# sim900.net
KiCad netlist of a schematic drawn in EAGLE
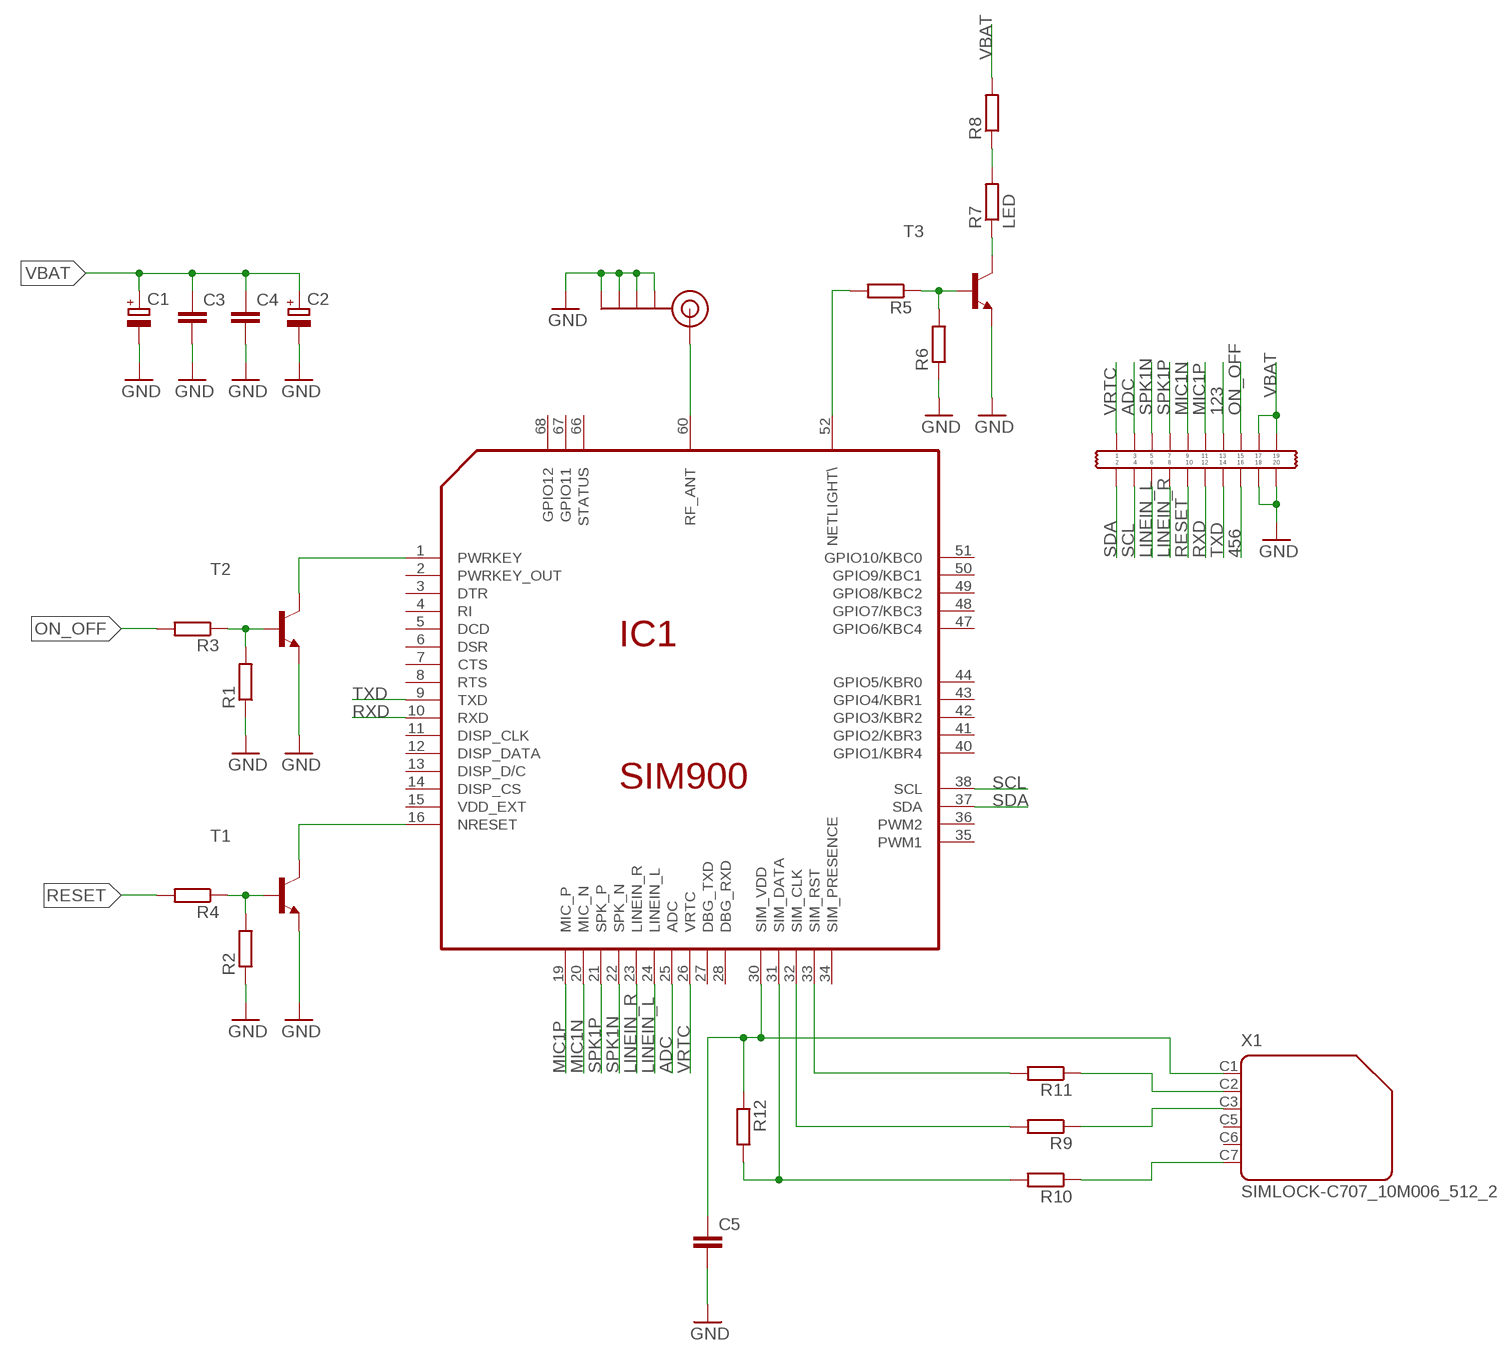
[diagram p0: schematic, sheet 1]

(export (version "E")
  (design (tool "Eeschema 10.0.6"))
  (components
    (comp (ref "C1")
      (value "CPOL-EUSMCD")
      (footprint "eagle-import:SMC_D")
      (libsource (lib "eagle-import") (part "CPOL-EUSMCD"))
    )
    (comp (ref "C2")
      (value "CPOL-EUSMCD")
      (footprint "eagle-import:SMC_D")
      (libsource (lib "eagle-import") (part "CPOL-EUSMCD"))
    )
    (comp (ref "C3")
      (value "C-EUC0805K")
      (footprint "eagle-import:C0805K")
      (libsource (lib "eagle-import") (part "C-EUC0805K"))
    )
    (comp (ref "C4")
      (value "C-EUC0805K")
      (footprint "eagle-import:C0805K")
      (libsource (lib "eagle-import") (part "C-EUC0805K"))
    )
    (comp (ref "C5")
      (value "C-EUC1206K")
      (footprint "eagle-import:C1206K")
      (libsource (lib "eagle-import") (part "C-EUC1206K"))
    )
    (comp (ref "IC1")
      (value "SIM900")
      (footprint "eagle-import:SIM900")
      (libsource (lib "eagle-import") (part "SIM900"))
    )
    (comp (ref "J$1")
      (value "SMA_EDGE")
      (footprint "eagle-import:SMA-EDGE")
      (libsource (lib "eagle-import") (part "SMA_EDGE"))
    )
    (comp (ref "R1")
      (value "R-EU_R0805")
      (footprint "eagle-import:R0805")
      (libsource (lib "eagle-import") (part "R-EU_R0805"))
    )
    (comp (ref "R2")
      (value "R-EU_R0805")
      (footprint "eagle-import:R0805")
      (libsource (lib "eagle-import") (part "R-EU_R0805"))
    )
    (comp (ref "R3")
      (value "R-EU_R0805")
      (footprint "eagle-import:R0805")
      (libsource (lib "eagle-import") (part "R-EU_R0805"))
    )
    (comp (ref "R4")
      (value "R-EU_R0805")
      (footprint "eagle-import:R0805")
      (libsource (lib "eagle-import") (part "R-EU_R0805"))
    )
    (comp (ref "R5")
      (value "R-EU_R0805")
      (footprint "eagle-import:R0805")
      (libsource (lib "eagle-import") (part "R-EU_R0805"))
    )
    (comp (ref "R6")
      (value "R-EU_R0805")
      (footprint "eagle-import:R0805")
      (libsource (lib "eagle-import") (part "R-EU_R0805"))
    )
    (comp (ref "R7")
      (value "LED")
      (footprint "eagle-import:R0805")
      (libsource (lib "eagle-import") (part "R-EU_R0805"))
    )
    (comp (ref "R8")
      (value "R-EU_R0805")
      (footprint "eagle-import:R0805")
      (libsource (lib "eagle-import") (part "R-EU_R0805"))
    )
    (comp (ref "R9")
      (value "R-EU_R0805")
      (footprint "eagle-import:R0805")
      (libsource (lib "eagle-import") (part "R-EU_R0805"))
    )
    (comp (ref "R10")
      (value "R-EU_R0805")
      (footprint "eagle-import:R0805")
      (libsource (lib "eagle-import") (part "R-EU_R0805"))
    )
    (comp (ref "R11")
      (value "R-EU_R0805")
      (footprint "eagle-import:R0805")
      (libsource (lib "eagle-import") (part "R-EU_R0805"))
    )
    (comp (ref "R12")
      (value "R-EU_R0805")
      (footprint "eagle-import:R0805")
      (libsource (lib "eagle-import") (part "R-EU_R0805"))
    )
    (comp (ref "T1")
      (value "-NPN-SOT23-EBC")
      (footprint "eagle-import:SOT23-EBC")
      (libsource (lib "eagle-import") (part "-NPN-SOT23-EBC"))
    )
    (comp (ref "T2")
      (value "-NPN-SOT23-EBC")
      (footprint "eagle-import:SOT23-EBC")
      (libsource (lib "eagle-import") (part "-NPN-SOT23-EBC"))
    )
    (comp (ref "T3")
      (value "-NPN-SOT23-EBC")
      (footprint "eagle-import:SOT23-EBC")
      (libsource (lib "eagle-import") (part "-NPN-SOT23-EBC"))
    )
    (comp (ref "U$1")
      (value "2X10")
      (footprint "eagle-import:2X10")
      (libsource (lib "eagle-import") (part "2X10"))
    )
    (comp (ref "X1")
      (value "SIMLOCK-C707_10M006_512_2")
      (footprint "eagle-import:C707_10M006_512_2")
      (libsource (lib "eagle-import") (part "SIMLOCK-C707_10M006_512_2"))
    )
  )
  (nets
    (net (code "1") (name "/123") (class "Default")
      (node (ref "U$1") (pin "T13") (pinfunction "C13_T13") (pintype "bidirectional"))
    )
    (net (code "2") (name "/456") (class "Default")
      (node (ref "U$1") (pin "B16") (pinfunction "C16_B16") (pintype "bidirectional"))
    )
    (net (code "3") (name "/ADC") (class "Default")
      (node (ref "IC1") (pin "25") (pinfunction "ADC_25") (pintype "bidirectional"))
      (node (ref "U$1") (pin "T3") (pinfunction "C3_T3") (pintype "bidirectional"))
    )
    (net (code "4") (name "/LINEIN_L") (class "Default")
      (node (ref "IC1") (pin "24") (pinfunction "LINEIN_L_24") (pintype "bidirectional"))
      (node (ref "U$1") (pin "B6") (pinfunction "C6_B6") (pintype "bidirectional"))
    )
    (net (code "5") (name "/LINEIN_R") (class "Default")
      (node (ref "IC1") (pin "23") (pinfunction "LINEIN_R_23") (pintype "bidirectional"))
      (node (ref "U$1") (pin "B8") (pinfunction "C8_B8") (pintype "bidirectional"))
    )
    (net (code "6") (name "/MIC1N") (class "Default")
      (node (ref "IC1") (pin "20") (pinfunction "MIC_N_20") (pintype "bidirectional"))
      (node (ref "U$1") (pin "T9") (pinfunction "C9_T9") (pintype "bidirectional"))
    )
    (net (code "7") (name "/MIC1P") (class "Default")
      (node (ref "IC1") (pin "19") (pinfunction "MIC_P_19") (pintype "bidirectional"))
      (node (ref "U$1") (pin "T11") (pinfunction "C11_T11") (pintype "bidirectional"))
    )
    (net (code "8") (name "/RXD") (class "Default")
      (node (ref "IC1") (pin "10") (pinfunction "RXD_10") (pintype "bidirectional"))
      (node (ref "U$1") (pin "B12") (pinfunction "C12_B12") (pintype "bidirectional"))
    )
    (net (code "9") (name "/SCL") (class "Default")
      (node (ref "IC1") (pin "38") (pinfunction "SCL_38") (pintype "bidirectional"))
      (node (ref "U$1") (pin "B4") (pinfunction "C4_B4") (pintype "bidirectional"))
    )
    (net (code "10") (name "/SDA") (class "Default")
      (node (ref "IC1") (pin "37") (pinfunction "SDA_37") (pintype "bidirectional"))
      (node (ref "U$1") (pin "B2") (pinfunction "C2_B2") (pintype "bidirectional"))
    )
    (net (code "11") (name "/SPK1N") (class "Default")
      (node (ref "IC1") (pin "22") (pinfunction "SPK_N_22") (pintype "bidirectional"))
      (node (ref "U$1") (pin "T5") (pinfunction "C5_T5") (pintype "bidirectional"))
    )
    (net (code "12") (name "/SPK1P") (class "Default")
      (node (ref "IC1") (pin "21") (pinfunction "SPK_P_21") (pintype "bidirectional"))
      (node (ref "U$1") (pin "T7") (pinfunction "C7_T7") (pintype "bidirectional"))
    )
    (net (code "13") (name "/TXD") (class "Default")
      (node (ref "IC1") (pin "9") (pinfunction "TXD_9") (pintype "bidirectional"))
      (node (ref "U$1") (pin "B14") (pinfunction "C14_B14") (pintype "bidirectional"))
    )
    (net (code "14") (name "/VRTC") (class "Default")
      (node (ref "IC1") (pin "26") (pinfunction "VRTC_26") (pintype "bidirectional"))
      (node (ref "U$1") (pin "T1") (pinfunction "C1_T1") (pintype "bidirectional"))
    )
    (net (code "15") (name "GND") (class "Default")
      (node (ref "C1") (pin "-") (pinfunction "-_-") (pintype "passive"))
      (node (ref "C2") (pin "-") (pinfunction "-_-") (pintype "passive"))
      (node (ref "C3") (pin "2") (pinfunction "2_2") (pintype "passive"))
      (node (ref "C4") (pin "2") (pinfunction "2_2") (pintype "passive"))
      (node (ref "C5") (pin "2") (pinfunction "2_2") (pintype "passive"))
      (node (ref "J$1") (pin "GND@0") (pinfunction "GND_GND@0") (pintype "bidirectional"))
      (node (ref "J$1") (pin "GND@1") (pinfunction "GND_GND@1") (pintype "bidirectional"))
      (node (ref "J$1") (pin "GND@2") (pinfunction "GND_GND@2") (pintype "bidirectional"))
      (node (ref "J$1") (pin "GND@3") (pinfunction "GND_GND@3") (pintype "bidirectional"))
      (node (ref "R1") (pin "1") (pinfunction "1_1") (pintype "passive"))
      (node (ref "R2") (pin "1") (pinfunction "1_1") (pintype "passive"))
      (node (ref "R6") (pin "1") (pinfunction "1_1") (pintype "passive"))
      (node (ref "T1") (pin "E") (pinfunction "E_E") (pintype "passive"))
      (node (ref "T2") (pin "E") (pinfunction "E_E") (pintype "passive"))
      (node (ref "T3") (pin "E") (pinfunction "E_E") (pintype "passive"))
      (node (ref "U$1") (pin "B18") (pinfunction "C18_B18") (pintype "bidirectional"))
      (node (ref "U$1") (pin "B20") (pinfunction "C20_B20") (pintype "bidirectional"))
    )
    (net (code "16") (name "Net-(IC1A-NETLIGHT\\)") (class "Default")
      (node (ref "IC1") (pin "52") (pinfunction "NETLIGHT\\_52") (pintype "bidirectional"))
      (node (ref "R5") (pin "2") (pinfunction "2_2") (pintype "passive"))
    )
    (net (code "17") (name "Net-(IC1A-NRESET)") (class "Default")
      (node (ref "IC1") (pin "16") (pinfunction "NRESET_16") (pintype "bidirectional"))
      (node (ref "T1") (pin "C") (pinfunction "C_C") (pintype "passive"))
    )
    (net (code "18") (name "Net-(IC1A-PWRKEY)") (class "Default")
      (node (ref "IC1") (pin "1") (pinfunction "PWRKEY_1") (pintype "bidirectional"))
      (node (ref "T2") (pin "C") (pinfunction "C_C") (pintype "passive"))
    )
    (net (code "19") (name "Net-(IC1A-RF_ANT)") (class "Default")
      (node (ref "IC1") (pin "60") (pinfunction "RF_ANT_60") (pintype "bidirectional"))
      (node (ref "J$1") (pin "SIG") (pinfunction "SIGNAL_SIG") (pintype "bidirectional"))
    )
    (net (code "20") (name "Net-(IC1A-SIM_CLK)") (class "Default")
      (node (ref "IC1") (pin "32") (pinfunction "SIM_CLK_32") (pintype "bidirectional"))
      (node (ref "R9") (pin "2") (pinfunction "2_2") (pintype "passive"))
    )
    (net (code "21") (name "Net-(IC1A-SIM_DATA)") (class "Default")
      (node (ref "IC1") (pin "31") (pinfunction "SIM_DATA_31") (pintype "bidirectional"))
      (node (ref "R10") (pin "2") (pinfunction "2_2") (pintype "passive"))
      (node (ref "R12") (pin "2") (pinfunction "2_2") (pintype "passive"))
    )
    (net (code "22") (name "Net-(IC1A-SIM_RST)") (class "Default")
      (node (ref "IC1") (pin "33") (pinfunction "SIM_RST_33") (pintype "bidirectional"))
      (node (ref "R11") (pin "2") (pinfunction "2_2") (pintype "passive"))
    )
    (net (code "23") (name "Net-(IC1A-SIM_VDD)") (class "Default")
      (node (ref "C5") (pin "1") (pinfunction "1_1") (pintype "passive"))
      (node (ref "IC1") (pin "30") (pinfunction "SIM_VDD_30") (pintype "bidirectional"))
      (node (ref "R12") (pin "1") (pinfunction "1_1") (pintype "passive"))
      (node (ref "X1") (pin "C1") (pinfunction "1_C1") (pintype "passive"))
    )
    (net (code "24") (name "Net-(R1-Pad2)") (class "Default")
      (node (ref "R1") (pin "2") (pinfunction "2_2") (pintype "passive"))
      (node (ref "R3") (pin "1") (pinfunction "1_1") (pintype "passive"))
      (node (ref "T2") (pin "B") (pinfunction "B_B") (pintype "passive"))
    )
    (net (code "25") (name "Net-(R2-Pad2)") (class "Default")
      (node (ref "R2") (pin "2") (pinfunction "2_2") (pintype "passive"))
      (node (ref "R4") (pin "1") (pinfunction "1_1") (pintype "passive"))
      (node (ref "T1") (pin "B") (pinfunction "B_B") (pintype "passive"))
    )
    (net (code "26") (name "Net-(R5-Pad1)") (class "Default")
      (node (ref "R5") (pin "1") (pinfunction "1_1") (pintype "passive"))
      (node (ref "R6") (pin "2") (pinfunction "2_2") (pintype "passive"))
      (node (ref "T3") (pin "B") (pinfunction "B_B") (pintype "passive"))
    )
    (net (code "27") (name "Net-(R7-Pad1)") (class "Default")
      (node (ref "R7") (pin "1") (pinfunction "1_1") (pintype "passive"))
      (node (ref "T3") (pin "C") (pinfunction "C_C") (pintype "passive"))
    )
    (net (code "28") (name "Net-(R7-Pad2)") (class "Default")
      (node (ref "R7") (pin "2") (pinfunction "2_2") (pintype "passive"))
      (node (ref "R8") (pin "1") (pinfunction "1_1") (pintype "passive"))
    )
    (net (code "29") (name "Net-(X1-2)") (class "Default")
      (node (ref "R11") (pin "1") (pinfunction "1_1") (pintype "passive"))
      (node (ref "X1") (pin "C2") (pinfunction "2_C2") (pintype "passive"))
    )
    (net (code "30") (name "Net-(X1-3)") (class "Default")
      (node (ref "R9") (pin "1") (pinfunction "1_1") (pintype "passive"))
      (node (ref "X1") (pin "C3") (pinfunction "3_C3") (pintype "passive"))
    )
    (net (code "31") (name "Net-(X1-6)") (class "Default")
      (node (ref "R10") (pin "1") (pinfunction "1_1") (pintype "passive"))
      (node (ref "X1") (pin "C7") (pinfunction "6_C7") (pintype "passive"))
    )
    (net (code "32") (name "ON_OFF") (class "Default")
      (node (ref "R3") (pin "2") (pinfunction "2_2") (pintype "passive"))
      (node (ref "U$1") (pin "T15") (pinfunction "C15_T15") (pintype "bidirectional"))
    )
    (net (code "33") (name "RESET") (class "Default")
      (node (ref "R4") (pin "2") (pinfunction "2_2") (pintype "passive"))
      (node (ref "U$1") (pin "B10") (pinfunction "C10_B10") (pintype "bidirectional"))
    )
    (net (code "34") (name "VBAT") (class "Default")
      (node (ref "C1") (pin "+") (pinfunction "+_+") (pintype "passive"))
      (node (ref "C2") (pin "+") (pinfunction "+_+") (pintype "passive"))
      (node (ref "C3") (pin "1") (pinfunction "1_1") (pintype "passive"))
      (node (ref "C4") (pin "1") (pinfunction "1_1") (pintype "passive"))
      (node (ref "R8") (pin "2") (pinfunction "2_2") (pintype "passive"))
      (node (ref "U$1") (pin "T17") (pinfunction "C17_T17") (pintype "bidirectional"))
      (node (ref "U$1") (pin "T19") (pinfunction "C19_T19") (pintype "bidirectional"))
    )
    (net (code "35") (name "unconnected-(IC1A-CTS-Pad7)") (class "Default")
      (node (ref "IC1") (pin "7") (pinfunction "CTS_7") (pintype "bidirectional"))
    )
    (net (code "36") (name "unconnected-(IC1A-DBG_RXD-Pad28)") (class "Default")
      (node (ref "IC1") (pin "28") (pinfunction "DBG_RXD_28") (pintype "bidirectional"))
    )
    (net (code "37") (name "unconnected-(IC1A-DBG_TXD-Pad27)") (class "Default")
      (node (ref "IC1") (pin "27") (pinfunction "DBG_TXD_27") (pintype "bidirectional"))
    )
    (net (code "38") (name "unconnected-(IC1A-DCD-Pad5)") (class "Default")
      (node (ref "IC1") (pin "5") (pinfunction "DCD_5") (pintype "bidirectional"))
    )
    (net (code "39") (name "unconnected-(IC1A-DISP_CLK-Pad11)") (class "Default")
      (node (ref "IC1") (pin "11") (pinfunction "DISP_CLK_11") (pintype "bidirectional"))
    )
    (net (code "40") (name "unconnected-(IC1A-DISP_CS-Pad14)") (class "Default")
      (node (ref "IC1") (pin "14") (pinfunction "DISP_CS_14") (pintype "bidirectional"))
    )
    (net (code "41") (name "unconnected-(IC1A-DISP_DATA-Pad12)") (class "Default")
      (node (ref "IC1") (pin "12") (pinfunction "DISP_DATA_12") (pintype "bidirectional"))
    )
    (net (code "42") (name "unconnected-(IC1A-DISP_D{slash}C-Pad13)") (class "Default")
      (node (ref "IC1") (pin "13") (pinfunction "DISP_D/C_13") (pintype "bidirectional"))
    )
    (net (code "43") (name "unconnected-(IC1A-DSR-Pad6)") (class "Default")
      (node (ref "IC1") (pin "6") (pinfunction "DSR_6") (pintype "bidirectional"))
    )
    (net (code "44") (name "unconnected-(IC1A-DTR-Pad3)") (class "Default")
      (node (ref "IC1") (pin "3") (pinfunction "DTR_3") (pintype "bidirectional"))
    )
    (net (code "45") (name "unconnected-(IC1A-GPIO1{slash}KBR4-Pad40)") (class "Default")
      (node (ref "IC1") (pin "40") (pinfunction "GPIO1/KBR4_40") (pintype "bidirectional"))
    )
    (net (code "46") (name "unconnected-(IC1A-GPIO2{slash}KBR3-Pad41)") (class "Default")
      (node (ref "IC1") (pin "41") (pinfunction "GPIO2/KBR3_41") (pintype "bidirectional"))
    )
    (net (code "47") (name "unconnected-(IC1A-GPIO3{slash}KBR2-Pad42)") (class "Default")
      (node (ref "IC1") (pin "42") (pinfunction "GPIO3/KBR2_42") (pintype "bidirectional"))
    )
    (net (code "48") (name "unconnected-(IC1A-GPIO4{slash}KBR1-Pad43)") (class "Default")
      (node (ref "IC1") (pin "43") (pinfunction "GPIO4/KBR1_43") (pintype "bidirectional"))
    )
    (net (code "49") (name "unconnected-(IC1A-GPIO5{slash}KBR0-Pad44)") (class "Default")
      (node (ref "IC1") (pin "44") (pinfunction "GPIO5/KBR0_44") (pintype "bidirectional"))
    )
    (net (code "50") (name "unconnected-(IC1A-GPIO6{slash}KBC4-Pad47)") (class "Default")
      (node (ref "IC1") (pin "47") (pinfunction "GPIO6/KBC4_47") (pintype "bidirectional"))
    )
    (net (code "51") (name "unconnected-(IC1A-GPIO7{slash}KBC3-Pad48)") (class "Default")
      (node (ref "IC1") (pin "48") (pinfunction "GPIO7/KBC3_48") (pintype "bidirectional"))
    )
    (net (code "52") (name "unconnected-(IC1A-GPIO8{slash}KBC2-Pad49)") (class "Default")
      (node (ref "IC1") (pin "49") (pinfunction "GPIO8/KBC2_49") (pintype "bidirectional"))
    )
    (net (code "53") (name "unconnected-(IC1A-GPIO9{slash}KBC1-Pad50)") (class "Default")
      (node (ref "IC1") (pin "50") (pinfunction "GPIO9/KBC1_50") (pintype "bidirectional"))
    )
    (net (code "54") (name "unconnected-(IC1A-GPIO10{slash}KBC0-Pad51)") (class "Default")
      (node (ref "IC1") (pin "51") (pinfunction "GPIO10/KBC0_51") (pintype "bidirectional"))
    )
    (net (code "55") (name "unconnected-(IC1A-GPIO11-Pad67)") (class "Default")
      (node (ref "IC1") (pin "67") (pinfunction "GPIO11_67") (pintype "bidirectional"))
    )
    (net (code "56") (name "unconnected-(IC1A-GPIO12-Pad68)") (class "Default")
      (node (ref "IC1") (pin "68") (pinfunction "GPIO12_68") (pintype "bidirectional"))
    )
    (net (code "57") (name "unconnected-(IC1A-PWM1-Pad35)") (class "Default")
      (node (ref "IC1") (pin "35") (pinfunction "PWM1_35") (pintype "bidirectional"))
    )
    (net (code "58") (name "unconnected-(IC1A-PWM2-Pad36)") (class "Default")
      (node (ref "IC1") (pin "36") (pinfunction "PWM2_36") (pintype "bidirectional"))
    )
    (net (code "59") (name "unconnected-(IC1A-PWRKEY_OUT-Pad2)") (class "Default")
      (node (ref "IC1") (pin "2") (pinfunction "PWRKEY_OUT_2") (pintype "bidirectional"))
    )
    (net (code "60") (name "unconnected-(IC1A-RI-Pad4)") (class "Default")
      (node (ref "IC1") (pin "4") (pinfunction "RI_4") (pintype "bidirectional"))
    )
    (net (code "61") (name "unconnected-(IC1A-RTS-Pad8)") (class "Default")
      (node (ref "IC1") (pin "8") (pinfunction "RTS_8") (pintype "bidirectional"))
    )
    (net (code "62") (name "unconnected-(IC1A-SIM_PRESENCE-Pad34)") (class "Default")
      (node (ref "IC1") (pin "34") (pinfunction "SIM_PRESENCE_34") (pintype "bidirectional"))
    )
    (net (code "63") (name "unconnected-(IC1A-STATUS-Pad66)") (class "Default")
      (node (ref "IC1") (pin "66") (pinfunction "STATUS_66") (pintype "bidirectional"))
    )
    (net (code "64") (name "unconnected-(IC1A-VDD_EXT-Pad15)") (class "Default")
      (node (ref "IC1") (pin "15") (pinfunction "VDD_EXT_15") (pintype "bidirectional"))
    )
    (net (code "65") (name "unconnected-(X1-4-PadC5)") (class "Default")
      (node (ref "X1") (pin "C5") (pinfunction "4_C5") (pintype "passive"))
    )
    (net (code "66") (name "unconnected-(X1-5-PadC6)") (class "Default")
      (node (ref "X1") (pin "C6") (pinfunction "5_C6") (pintype "passive"))
    )
  )
)
